# PSU_TC1017R_3V3.net
KiCad netlist of a schematic drawn in Altium Designer
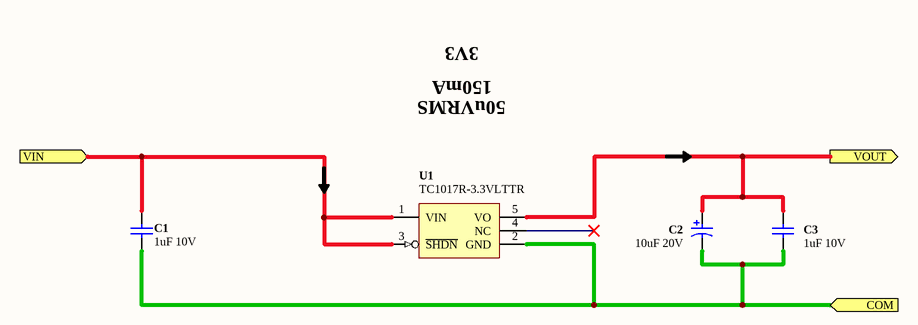
[diagram p0: PSU_TC1017R_3V3.SchDoc]

(export (version "E")
  (design (tool "Eeschema 10.0.6"))
  (components
    (comp (ref "C1")
      (value "1uF 10V")
      (footprint "CAPC1005-STAR")
      (description "Capacitor, Ceramic, 1uF 10% 10V 0402 (1005) X5R")
      (fields (field (name "TOLERANCE") "10 %"))
      (libsource (lib "AltiumDesignLibrary") (part "CAP-NP"))
    )
    (comp (ref "C2")
      (value "10uF 20V")
      (footprint "CAPC3528-STAR")
      (description "Capacitor, Tantalum, 10uF 10% 20V MCCT-B (3528)")
      (fields (field (name "TOLERANCE") "10 %"))
      (libsource (lib "AltiumDesignLibrary") (part "CAP-P"))
    )
    (comp (ref "C3")
      (value "1uF 10V")
      (footprint "CAPC1005-STAR")
      (description "Capacitor, Ceramic, 1uF 10% 10V 0402 (1005) X5R")
      (fields (field (name "TOLERANCE") "10 %"))
      (libsource (lib "AltiumDesignLibrary") (part "CAP-NP"))
    )
    (comp (ref "U1")
      (value "TC1017R-3.3VLTTR")
      (footprint "SOT65P210X80-5N")
      (description "TC1017R-3.3VLTTR, 3.3V Micropower Low Dropout Regulator, 5-Pin SC70-5")
      (libsource (lib "AltiumDesignLibrary") (part "TC1017R"))
    )
  )
  (nets
    (net (code "1") (name "/COM") (class "Default")
      (node (ref "C1") (pin "1") (pinfunction "1_1") (pintype "passive"))
      (node (ref "C2") (pin "2") (pinfunction "2_2") (pintype "passive"))
      (node (ref "C3") (pin "1") (pinfunction "1_1") (pintype "passive"))
      (node (ref "U1") (pin "2") (pinfunction "GND_2") (pintype "power_in"))
    )
    (net (code "2") (name "/VIN") (class "Default")
      (node (ref "C1") (pin "2") (pinfunction "2_2") (pintype "passive"))
      (node (ref "U1") (pin "1") (pinfunction "VIN_1") (pintype "power_in"))
      (node (ref "U1") (pin "3") (pinfunction "~{SHDN}_3") (pintype "input"))
    )
    (net (code "3") (name "/VOUT") (class "Default")
      (node (ref "C2") (pin "1") (pinfunction "1_1") (pintype "passive"))
      (node (ref "C3") (pin "2") (pinfunction "2_2") (pintype "passive"))
      (node (ref "U1") (pin "5") (pinfunction "VO_5") (pintype "power_in"))
    )
    (net (code "4") (name "unconnected-(U1-NC-Pad4)") (class "Default")
      (node (ref "U1") (pin "4") (pinfunction "NC_4") (pintype "passive+no_connect"))
    )
  )
)
